# DRV5021A3QDBZR.net
KiCad netlist of a schematic drawn in Altium Designer
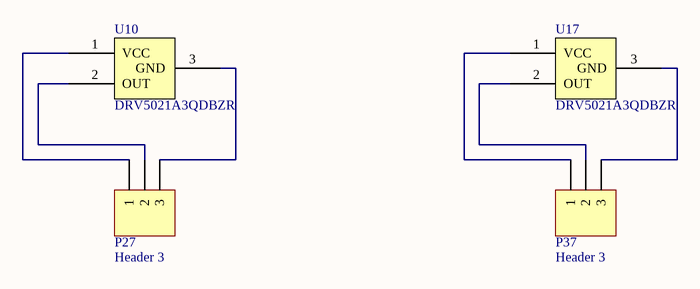
[diagram p0: DRV5021A3QDBZR.SchDoc]

(export (version "E")
  (design (tool "Eeschema 10.0.6"))
  (components
    (comp (ref "P27")
      (value "Header 3")
      (footprint "HDR1X3")
      (description "Header, 3-Pin")
      (fields (field (name "PUBLISHER") "Altium Limited"))
      (libsource (lib "Miscellaneous Connectors") (part "Header 3"))
    )
    (comp (ref "P37")
      (value "Header 3")
      (footprint "HDR1X3")
      (description "Header, 3-Pin")
      (fields (field (name "PUBLISHER") "Altium Limited"))
      (libsource (lib "Miscellaneous Connectors") (part "Header 3"))
    )
    (comp (ref "U10")
      (value "DRV5021A3QDBZR")
      (footprint "DRV5021A3QDBZR")
      (description "Hall effect IC")
      (libsource (lib "DRV5021A3QDBZR") (part "DRV5021A3QDBZR"))
    )
    (comp (ref "U17")
      (value "DRV5021A3QDBZR")
      (footprint "DRV5021A3QDBZR")
      (description "Hall effect IC")
      (libsource (lib "DRV5021A3QDBZR") (part "DRV5021A3QDBZR"))
    )
  )
  (nets
    (net (code "1") (name "Net-(U10-GND)") (class "Default")
      (node (ref "P27") (pin "3") (pinfunction "3_3") (pintype "passive"))
      (node (ref "U10") (pin "3") (pinfunction "GND_3") (pintype "passive"))
    )
    (net (code "2") (name "Net-(U10-OUT)") (class "Default")
      (node (ref "P27") (pin "2") (pinfunction "2_2") (pintype "passive"))
      (node (ref "U10") (pin "2") (pinfunction "OUT_2") (pintype "passive"))
    )
    (net (code "3") (name "Net-(U10-VCC)") (class "Default")
      (node (ref "P27") (pin "1") (pinfunction "1_1") (pintype "passive"))
      (node (ref "U10") (pin "1") (pinfunction "VCC_1") (pintype "passive"))
    )
    (net (code "4") (name "Net-(U17-GND)") (class "Default")
      (node (ref "P37") (pin "3") (pinfunction "3_3") (pintype "passive"))
      (node (ref "U17") (pin "3") (pinfunction "GND_3") (pintype "passive"))
    )
    (net (code "5") (name "Net-(U17-OUT)") (class "Default")
      (node (ref "P37") (pin "2") (pinfunction "2_2") (pintype "passive"))
      (node (ref "U17") (pin "2") (pinfunction "OUT_2") (pintype "passive"))
    )
    (net (code "6") (name "Net-(U17-VCC)") (class "Default")
      (node (ref "P37") (pin "1") (pinfunction "1_1") (pintype "passive"))
      (node (ref "U17") (pin "1") (pinfunction "VCC_1") (pintype "passive"))
    )
  )
)
